# HomeAtion_RemoteDHT.net
KiCad netlist of a schematic drawn in EAGLE
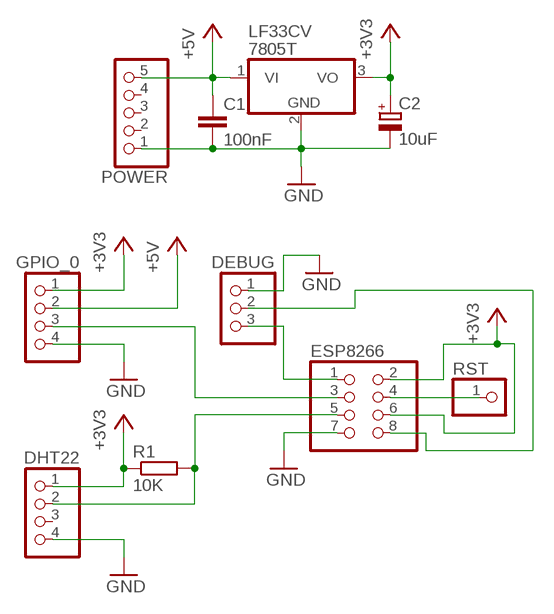
[diagram p0: schematic, sheet 1]

(export (version "E")
  (design (tool "Eeschema 10.0.6"))
  (components
    (comp (ref "C1")
      (value "100nF")
      (footprint "eagle-import:C2.5-5")
      (libsource (lib "eagle-import") (part "C2.5/5"))
    )
    (comp (ref "C2")
      (value "10uF")
      (footprint "eagle-import:B45181A")
      (libsource (lib "eagle-import") (part "CPOL-EUB45181A"))
    )
    (comp (ref "DEBUG")
      (value "PINHD-1X3")
      (footprint "eagle-import:1X03")
      (libsource (lib "eagle-import") (part "PINHD-1X3"))
    )
    (comp (ref "DHT22")
      (value "PINHD-1X4")
      (footprint "eagle-import:1X04")
      (libsource (lib "eagle-import") (part "PINHD-1X4"))
    )
    (comp (ref "ESP8266")
      (value "PINHD-2X4")
      (footprint "eagle-import:2X04")
      (libsource (lib "eagle-import") (part "PINHD-2X4"))
    )
    (comp (ref "GPIO_0")
      (value "PINHD-1X4")
      (footprint "eagle-import:1X04")
      (libsource (lib "eagle-import") (part "PINHD-1X4"))
    )
    (comp (ref "LF33CV")
      (value "7805T")
      (footprint "eagle-import:TO220H")
      (libsource (lib "eagle-import") (part "78T05"))
    )
    (comp (ref "POWER")
      (value "PINHD-1X5")
      (footprint "eagle-import:1X05")
      (libsource (lib "eagle-import") (part "PINHD-1X5"))
    )
    (comp (ref "R1")
      (value "10K")
      (footprint "eagle-import:0204_7")
      (libsource (lib "eagle-import") (part "R-EU_0204/7"))
    )
    (comp (ref "RST")
      (value "PINHD-1X1")
      (footprint "eagle-import:1X01")
      (libsource (lib "eagle-import") (part "PINHD-1X1"))
    )
  )
  (nets
    (net (code "1") (name "+3V3") (class "Default")
      (node (ref "C2") (pin "+") (pinfunction "+_+") (pintype "passive"))
      (node (ref "DHT22") (pin "1") (pinfunction "1_1") (pintype "passive"))
      (node (ref "ESP8266") (pin "2") (pinfunction "2_2") (pintype "passive"))
      (node (ref "ESP8266") (pin "6") (pinfunction "6_6") (pintype "passive"))
      (node (ref "GPIO_0") (pin "1") (pinfunction "1_1") (pintype "passive"))
      (node (ref "LF33CV") (pin "3") (pinfunction "VO_3") (pintype "passive"))
      (node (ref "R1") (pin "1") (pinfunction "1_1") (pintype "passive"))
    )
    (net (code "2") (name "+5V") (class "Default")
      (node (ref "C1") (pin "1") (pinfunction "1_1") (pintype "passive"))
      (node (ref "GPIO_0") (pin "2") (pinfunction "2_2") (pintype "passive"))
      (node (ref "LF33CV") (pin "1") (pinfunction "VI_1") (pintype "input"))
      (node (ref "POWER") (pin "5") (pinfunction "5_5") (pintype "passive"))
    )
    (net (code "3") (name "GND") (class "Default")
      (node (ref "C1") (pin "2") (pinfunction "2_2") (pintype "passive"))
      (node (ref "C2") (pin "-") (pinfunction "-_-") (pintype "passive"))
      (node (ref "DEBUG") (pin "1") (pinfunction "1_1") (pintype "passive"))
      (node (ref "DHT22") (pin "4") (pinfunction "4_4") (pintype "passive"))
      (node (ref "ESP8266") (pin "7") (pinfunction "7_7") (pintype "passive"))
      (node (ref "GPIO_0") (pin "4") (pinfunction "4_4") (pintype "passive"))
      (node (ref "LF33CV") (pin "2") (pinfunction "GND_2") (pintype "passive"))
      (node (ref "POWER") (pin "1") (pinfunction "1_1") (pintype "passive"))
    )
    (net (code "4") (name "Net-(DEBUG-Pad2)") (class "Default")
      (node (ref "DEBUG") (pin "2") (pinfunction "2_2") (pintype "passive"))
      (node (ref "ESP8266") (pin "8") (pinfunction "8_8") (pintype "passive"))
    )
    (net (code "5") (name "Net-(DEBUG-Pad3)") (class "Default")
      (node (ref "DEBUG") (pin "3") (pinfunction "3_3") (pintype "passive"))
      (node (ref "ESP8266") (pin "1") (pinfunction "1_1") (pintype "passive"))
    )
    (net (code "6") (name "Net-(DHT22-Pad2)") (class "Default")
      (node (ref "DHT22") (pin "2") (pinfunction "2_2") (pintype "passive"))
      (node (ref "ESP8266") (pin "5") (pinfunction "5_5") (pintype "passive"))
      (node (ref "R1") (pin "2") (pinfunction "2_2") (pintype "passive"))
    )
    (net (code "7") (name "Net-(ESP8266-Pad3)") (class "Default")
      (node (ref "ESP8266") (pin "3") (pinfunction "3_3") (pintype "passive"))
      (node (ref "GPIO_0") (pin "3") (pinfunction "3_3") (pintype "passive"))
    )
    (net (code "8") (name "Net-(ESP8266-Pad4)") (class "Default")
      (node (ref "ESP8266") (pin "4") (pinfunction "4_4") (pintype "passive"))
      (node (ref "RST") (pin "1") (pinfunction "1_1") (pintype "passive"))
    )
    (net (code "9") (name "unconnected-(DHT22-Pad3)") (class "Default")
      (node (ref "DHT22") (pin "3") (pinfunction "3_3") (pintype "passive"))
    )
    (net (code "10") (name "unconnected-(POWER-Pad2)") (class "Default")
      (node (ref "POWER") (pin "2") (pinfunction "2_2") (pintype "passive"))
    )
    (net (code "11") (name "unconnected-(POWER-Pad3)") (class "Default")
      (node (ref "POWER") (pin "3") (pinfunction "3_3") (pintype "passive"))
    )
    (net (code "12") (name "unconnected-(POWER-Pad4)") (class "Default")
      (node (ref "POWER") (pin "4") (pinfunction "4_4") (pintype "passive"))
    )
  )
)
